# LBriduino.net
KiCad netlist of a schematic drawn in EAGLE
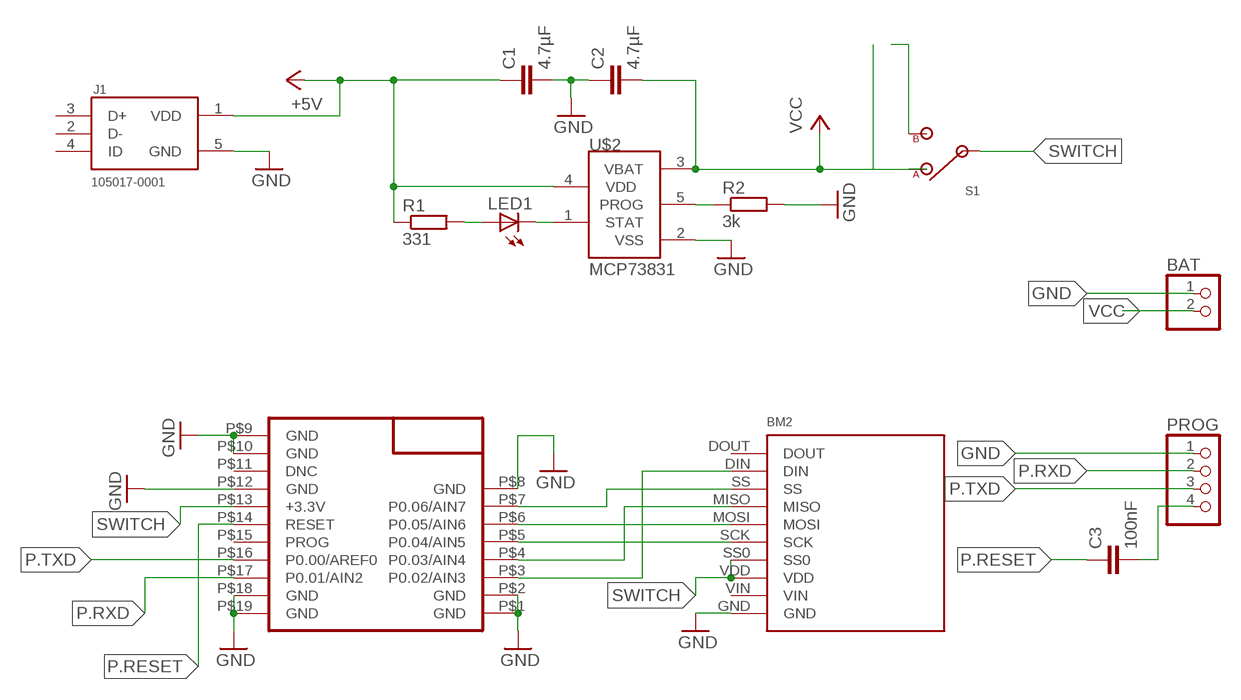
[diagram p0: schematic, sheet 1]

(export (version "E")
  (design (tool "Eeschema 10.0.6"))
  (components
    (comp (ref "BAT")
      (value "PINHD-1X2")
      (footprint "eagle-import:1X02")
      (libsource (lib "eagle-import") (part "PINHD-1X2"))
    )
    (comp (ref "BM2")
      (value "BM019")
      (footprint "eagle-import:BM019")
      (libsource (lib "eagle-import") (part "BM019"))
    )
    (comp (ref "C1")
      (value "4.7µF")
      (footprint "eagle-import:C0603")
      (libsource (lib "eagle-import") (part "C-EUC0603"))
    )
    (comp (ref "C2")
      (value "4.7µF")
      (footprint "eagle-import:C0603")
      (libsource (lib "eagle-import") (part "C-EUC0603"))
    )
    (comp (ref "C3")
      (value "100nF")
      (footprint "eagle-import:C0603")
      (libsource (lib "eagle-import") (part "C-EUC0603"))
    )
    (comp (ref "J1")
      (value "105017-0001")
      (footprint "eagle-import:MOLEX_105017-0001")
      (fields (field (name "MF") "Molex"))
      (libsource (lib "eagle-import") (part "105017-0001"))
    )
    (comp (ref "LED1")
      (value "LEDCHIP-LED0603")
      (footprint "eagle-import:CHIP-LED0603")
      (libsource (lib "eagle-import") (part "LEDCHIP-LED0603"))
    )
    (comp (ref "PROG")
      (value "PINHD-1X4")
      (footprint "eagle-import:1X04")
      (libsource (lib "eagle-import") (part "PINHD-1X4"))
    )
    (comp (ref "R1")
      (value "331")
      (footprint "eagle-import:R0603")
      (libsource (lib "eagle-import") (part "R-EU_R0603"))
    )
    (comp (ref "R2")
      (value "3k")
      (footprint "eagle-import:R0603")
      (libsource (lib "eagle-import") (part "R-EU_R0603"))
    )
    (comp (ref "S1")
      (value "STS121PC04")
      (footprint "eagle-import:STS121PC04")
      (libsource (lib "eagle-import") (part "STS121PC04"))
    )
    (comp (ref "U$1")
      (value "RFD22301")
      (footprint "eagle-import:RFD21733")
      (libsource (lib "eagle-import") (part "RFD22301"))
    )
    (comp (ref "U$2")
      (value "MCP73831")
      (footprint "eagle-import:SOT23-5L")
      (libsource (lib "eagle-import") (part "MCP73831"))
    )
  )
  (nets
    (net (code "1") (name "+5V") (class "Default")
      (node (ref "C1") (pin "1") (pinfunction "1_1") (pintype "passive"))
      (node (ref "J1") (pin "1") (pinfunction "VDD_1") (pintype "power_in"))
      (node (ref "R1") (pin "1") (pinfunction "1_1") (pintype "passive"))
      (node (ref "U$2") (pin "4") (pinfunction "VDD_4") (pintype "bidirectional"))
    )
    (net (code "2") (name "GND") (class "Default")
      (node (ref "BAT") (pin "1") (pinfunction "1_1") (pintype "passive"))
      (node (ref "BM2") (pin "GND") (pinfunction "GND_GND") (pintype "bidirectional"))
      (node (ref "C1") (pin "2") (pinfunction "2_2") (pintype "passive"))
      (node (ref "C2") (pin "1") (pinfunction "1_1") (pintype "passive"))
      (node (ref "J1") (pin "5") (pinfunction "GND_5") (pintype "power_in"))
      (node (ref "PROG") (pin "1") (pinfunction "1_1") (pintype "passive"))
      (node (ref "R2") (pin "2") (pinfunction "2_2") (pintype "passive"))
      (node (ref "U$1") (pin "P$1") (pinfunction "GND_P$1") (pintype "bidirectional"))
      (node (ref "U$1") (pin "P$10") (pinfunction "GND_P$10") (pintype "bidirectional"))
      (node (ref "U$1") (pin "P$12") (pinfunction "GND_P$12") (pintype "bidirectional"))
      (node (ref "U$1") (pin "P$18") (pinfunction "GND_P$18") (pintype "bidirectional"))
      (node (ref "U$1") (pin "P$19") (pinfunction "GND_P$19") (pintype "bidirectional"))
      (node (ref "U$1") (pin "P$2") (pinfunction "GND_P$2") (pintype "bidirectional"))
      (node (ref "U$1") (pin "P$8") (pinfunction "GND_P$8") (pintype "bidirectional"))
      (node (ref "U$1") (pin "P$9") (pinfunction "GND_P$9") (pintype "bidirectional"))
      (node (ref "U$2") (pin "2") (pinfunction "VSS_2") (pintype "bidirectional"))
    )
    (net (code "3") (name "Net-(C3-Pad2)") (class "Default")
      (node (ref "C3") (pin "2") (pinfunction "2_2") (pintype "passive"))
      (node (ref "PROG") (pin "4") (pinfunction "4_4") (pintype "passive"))
    )
    (net (code "4") (name "Net-(LED1-PadA)") (class "Default")
      (node (ref "LED1") (pin "A") (pinfunction "A_A") (pintype "passive"))
      (node (ref "R1") (pin "2") (pinfunction "2_2") (pintype "passive"))
    )
    (net (code "5") (name "Net-(U$1-P0.02{slash}AIN3)") (class "Default")
      (node (ref "BM2") (pin "DIN") (pinfunction "DIN_DIN") (pintype "bidirectional"))
      (node (ref "U$1") (pin "P$3") (pinfunction "P0.02/AIN3_P$3") (pintype "bidirectional"))
    )
    (net (code "6") (name "Net-(U$1-P0.03{slash}AIN4)") (class "Default")
      (node (ref "BM2") (pin "MISO") (pinfunction "MISO_MISO") (pintype "bidirectional"))
      (node (ref "U$1") (pin "P$4") (pinfunction "P0.03/AIN4_P$4") (pintype "bidirectional"))
    )
    (net (code "7") (name "Net-(U$1-P0.04{slash}AIN5)") (class "Default")
      (node (ref "BM2") (pin "SCK") (pinfunction "SCK_SCK") (pintype "bidirectional"))
      (node (ref "U$1") (pin "P$5") (pinfunction "P0.04/AIN5_P$5") (pintype "bidirectional"))
    )
    (net (code "8") (name "Net-(U$1-P0.05{slash}AIN6)") (class "Default")
      (node (ref "BM2") (pin "MOSI") (pinfunction "MOSI_MOSI") (pintype "bidirectional"))
      (node (ref "U$1") (pin "P$6") (pinfunction "P0.05/AIN6_P$6") (pintype "bidirectional"))
    )
    (net (code "9") (name "Net-(U$1-P0.06{slash}AIN7)") (class "Default")
      (node (ref "BM2") (pin "SS") (pinfunction "SS_SS") (pintype "bidirectional"))
      (node (ref "U$1") (pin "P$7") (pinfunction "P0.06/AIN7_P$7") (pintype "bidirectional"))
    )
    (net (code "10") (name "Net-(U$2-PROG)") (class "Default")
      (node (ref "R2") (pin "1") (pinfunction "1_1") (pintype "passive"))
      (node (ref "U$2") (pin "5") (pinfunction "PROG_5") (pintype "bidirectional"))
    )
    (net (code "11") (name "Net-(U$2-STAT)") (class "Default")
      (node (ref "LED1") (pin "C") (pinfunction "C_C") (pintype "passive"))
      (node (ref "U$2") (pin "1") (pinfunction "STAT_1") (pintype "bidirectional"))
    )
    (net (code "12") (name "P.RESET") (class "Default")
      (node (ref "C3") (pin "1") (pinfunction "1_1") (pintype "passive"))
      (node (ref "U$1") (pin "P$14") (pinfunction "RESET_P$14") (pintype "bidirectional"))
    )
    (net (code "13") (name "P.RXD") (class "Default")
      (node (ref "PROG") (pin "2") (pinfunction "2_2") (pintype "passive"))
      (node (ref "U$1") (pin "P$17") (pinfunction "P0.01/AIN2_P$17") (pintype "bidirectional"))
    )
    (net (code "14") (name "P.TXD") (class "Default")
      (node (ref "PROG") (pin "3") (pinfunction "3_3") (pintype "passive"))
      (node (ref "U$1") (pin "P$16") (pinfunction "P0.00/AREF0_P$16") (pintype "bidirectional"))
    )
    (net (code "15") (name "SWITCH") (class "Default")
      (node (ref "BM2") (pin "SS0") (pinfunction "SS0_SS0") (pintype "bidirectional"))
      (node (ref "BM2") (pin "VDD") (pinfunction "VDD_VDD") (pintype "bidirectional"))
      (node (ref "S1") (pin "2") (pinfunction "2_2") (pintype "bidirectional"))
      (node (ref "U$1") (pin "P$13") (pinfunction "+3.3V_P$13") (pintype "bidirectional"))
    )
    (net (code "16") (name "VCC") (class "Default")
      (node (ref "BAT") (pin "2") (pinfunction "2_2") (pintype "passive"))
      (node (ref "C2") (pin "2") (pinfunction "2_2") (pintype "passive"))
      (node (ref "S1") (pin "1") (pinfunction "1_1") (pintype "bidirectional"))
      (node (ref "U$2") (pin "3") (pinfunction "VBAT_3") (pintype "bidirectional"))
    )
    (net (code "17") (name "unconnected-(BM2-PadDOUT)") (class "Default")
      (node (ref "BM2") (pin "DOUT") (pinfunction "DOUT_DOUT") (pintype "bidirectional"))
    )
    (net (code "18") (name "unconnected-(BM2-PadVIN)") (class "Default")
      (node (ref "BM2") (pin "VIN") (pinfunction "VIN_VIN") (pintype "bidirectional"))
    )
    (net (code "19") (name "unconnected-(J1-D+-Pad3)") (class "Default")
      (node (ref "J1") (pin "3") (pinfunction "D+_3") (pintype "bidirectional"))
    )
    (net (code "20") (name "unconnected-(J1-D--Pad2)") (class "Default")
      (node (ref "J1") (pin "2") (pinfunction "D-_2") (pintype "bidirectional"))
    )
    (net (code "21") (name "unconnected-(J1-ID-Pad4)") (class "Default")
      (node (ref "J1") (pin "4") (pinfunction "ID_4") (pintype "passive"))
    )
    (net (code "22") (name "unconnected-(S1-Pad3)") (class "Default")
      (node (ref "S1") (pin "3") (pinfunction "3_3") (pintype "bidirectional"))
    )
    (net (code "23") (name "unconnected-(U$1-DNC-PadP$11)") (class "Default")
      (node (ref "U$1") (pin "P$11") (pinfunction "DNC_P$11") (pintype "bidirectional"))
    )
    (net (code "24") (name "unconnected-(U$1-PROG-PadP$15)") (class "Default")
      (node (ref "U$1") (pin "P$15") (pinfunction "PROG_P$15") (pintype "bidirectional"))
    )
  )
)
